# pong.net
KiCad netlist of a schematic drawn in EAGLE
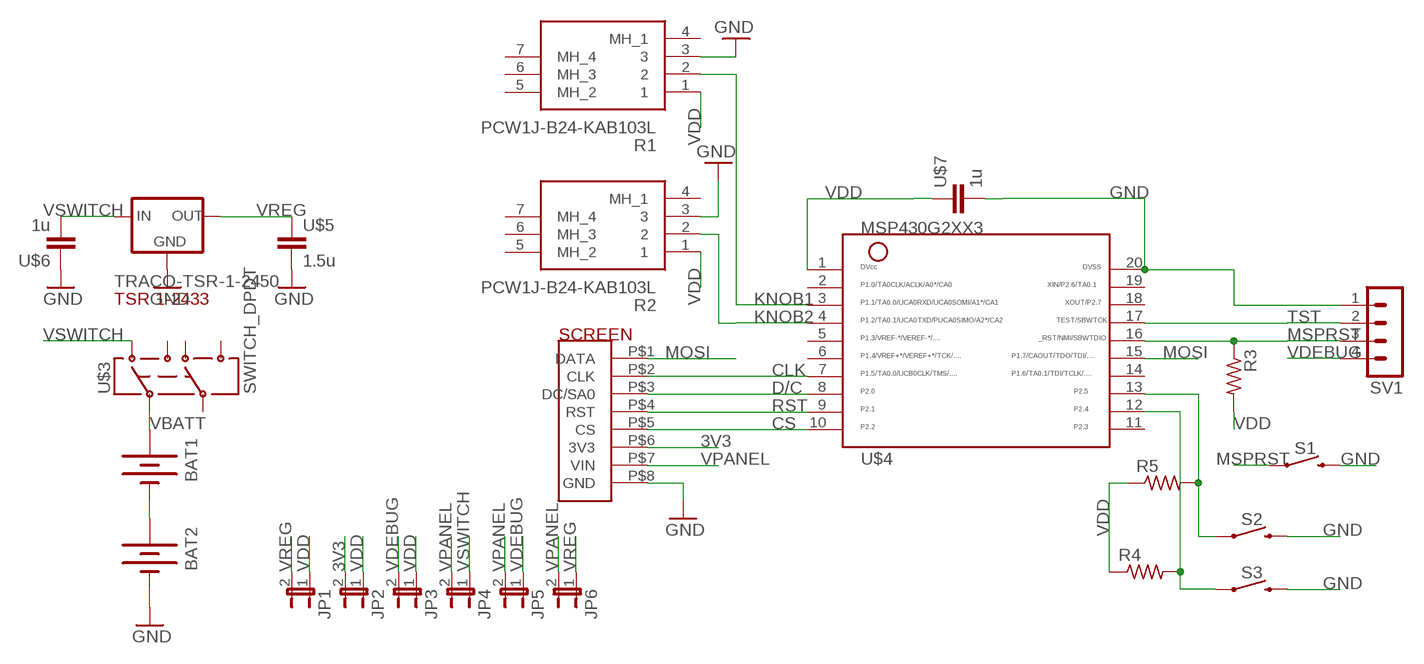
[diagram p0: schematic, sheet 1]

(export (version "E")
  (design (tool "Eeschema 10.0.6"))
  (components
    (comp (ref "BAT1")
      (value "BATTERY")
      (footprint "eagle-import:BATTERY_PACK_2AA")
      (libsource (lib "eagle-import") (part "BATTERY"))
    )
    (comp (ref "BAT2")
      (value "BATTERY")
      (footprint "eagle-import:BATTERY_PACK_2AA")
      (libsource (lib "eagle-import") (part "BATTERY"))
    )
    (comp (ref "JP1")
      (value "JP1E")
      (footprint "eagle-import:JP1")
      (libsource (lib "eagle-import") (part "JP1E"))
    )
    (comp (ref "JP2")
      (value "JP1E")
      (footprint "eagle-import:JP1")
      (libsource (lib "eagle-import") (part "JP1E"))
    )
    (comp (ref "JP3")
      (value "JP1E")
      (footprint "eagle-import:JP1")
      (libsource (lib "eagle-import") (part "JP1E"))
    )
    (comp (ref "JP4")
      (value "JP1E")
      (footprint "eagle-import:JP1")
      (libsource (lib "eagle-import") (part "JP1E"))
    )
    (comp (ref "JP5")
      (value "JP1E")
      (footprint "eagle-import:JP1")
      (libsource (lib "eagle-import") (part "JP1E"))
    )
    (comp (ref "JP6")
      (value "JP1E")
      (footprint "eagle-import:JP1")
      (libsource (lib "eagle-import") (part "JP1E"))
    )
    (comp (ref "R1")
      (value "PCW1J-B24-KAB103L")
      (footprint "eagle-import:PCW1JB24KAB103L")
      (fields
        (field (name "MOUSER_PART_NUMBER") "652-PCW1JB24KAB103L")
        (field (name "RS_PART_NUMBER") "1674561")
      )
      (libsource (lib "eagle-import") (part "PCW1J-B24-KAB103L"))
    )
    (comp (ref "R2")
      (value "PCW1J-B24-KAB103L")
      (footprint "eagle-import:PCW1JB24KAB103L")
      (fields
        (field (name "MOUSER_PART_NUMBER") "652-PCW1JB24KAB103L")
        (field (name "RS_PART_NUMBER") "1674561")
      )
      (libsource (lib "eagle-import") (part "PCW1J-B24-KAB103L"))
    )
    (comp (ref "R3")
      (value "47k")
      (footprint "eagle-import:R0805")
      (libsource (lib "eagle-import") (part "R-US_R0805"))
    )
    (comp (ref "R4")
      (value "47k")
      (footprint "eagle-import:R0805")
      (libsource (lib "eagle-import") (part "R-US_R0805"))
    )
    (comp (ref "R5")
      (value "47k")
      (footprint "eagle-import:R0805")
      (libsource (lib "eagle-import") (part "R-US_R0805"))
    )
    (comp (ref "S1")
      (value "MOMENTARY-SWITCH-SPST-PTH-6.0MM")
      (footprint "eagle-import:TACTILE_SWITCH_PTH_6.0MM")
      (libsource (lib "eagle-import") (part "MOMENTARY-SWITCH-SPST-PTH-6.0MM"))
    )
    (comp (ref "S2")
      (value "MOMENTARY-SWITCH-SPST-PTH-6.0MM")
      (footprint "eagle-import:TACTILE_SWITCH_PTH_6.0MM")
      (libsource (lib "eagle-import") (part "MOMENTARY-SWITCH-SPST-PTH-6.0MM"))
    )
    (comp (ref "S3")
      (value "MOMENTARY-SWITCH-SPST-PTH-6.0MM")
      (footprint "eagle-import:TACTILE_SWITCH_PTH_6.0MM")
      (libsource (lib "eagle-import") (part "MOMENTARY-SWITCH-SPST-PTH-6.0MM"))
    )
    (comp (ref "SV1")
      (value "4PINHEAD")
      (footprint "eagle-import:MA04-1")
      (libsource (lib "eagle-import") (part "4PINHEAD"))
    )
    (comp (ref "U$2")
      (value "SCREEN_HEADER")
      (footprint "eagle-import:SCREEN_FP")
      (libsource (lib "eagle-import") (part "SCREEN_HEADER"))
    )
    (comp (ref "U$3")
      (value "SWITCH_DPDT")
      (footprint "eagle-import:JS_DPDT_TH")
      (libsource (lib "eagle-import") (part "SWITCH_DPDT"))
    )
    (comp (ref "U$4")
      (value "MSP430G2XX3TSSOP")
      (footprint "eagle-import:PW20")
      (libsource (lib "eagle-import") (part "MSP430G2XX3TSSOP"))
    )
    (comp (ref "U$5")
      (value "1.5u")
      (footprint "eagle-import:RESC0805_N")
      (libsource (lib "eagle-import") (part "CAPACITOR_0805_N"))
    )
    (comp (ref "U$6")
      (value "1u")
      (footprint "eagle-import:RESC0805_N")
      (libsource (lib "eagle-import") (part "CAPACITOR_0805_N"))
    )
    (comp (ref "U$7")
      (value "1u")
      (footprint "eagle-import:RESC0805_N")
      (libsource (lib "eagle-import") (part "CAPACITOR_0805_N"))
    )
    (comp (ref "U$8")
      (value "TRACO-TSR-1-2450")
      (footprint "eagle-import:SIP3")
      (libsource (lib "eagle-import") (part "TRACO-TSR-1-2450"))
    )
  )
  (nets
    (net (code "1") (name "/3V3") (class "Default")
      (node (ref "JP2") (pin "2") (pinfunction "2_2") (pintype "passive"))
      (node (ref "U$2") (pin "P$6") (pinfunction "3V3_P$6") (pintype "bidirectional"))
    )
    (net (code "2") (name "/CLK") (class "Default")
      (node (ref "U$2") (pin "P$2") (pinfunction "CLK_P$2") (pintype "bidirectional"))
      (node (ref "U$4") (pin "7") (pinfunction "7_7") (pintype "bidirectional"))
    )
    (net (code "3") (name "/CS") (class "Default")
      (node (ref "U$2") (pin "P$5") (pinfunction "CS_P$5") (pintype "bidirectional"))
      (node (ref "U$4") (pin "10") (pinfunction "10_10") (pintype "bidirectional"))
    )
    (net (code "4") (name "/D{slash}C") (class "Default")
      (node (ref "U$2") (pin "P$3") (pinfunction "DC/SA0_P$3") (pintype "bidirectional"))
      (node (ref "U$4") (pin "8") (pinfunction "8_8") (pintype "bidirectional"))
    )
    (net (code "5") (name "/KNOB1") (class "Default")
      (node (ref "R1") (pin "2") (pinfunction "2_2") (pintype "bidirectional"))
      (node (ref "U$4") (pin "3") (pinfunction "3_3") (pintype "bidirectional"))
    )
    (net (code "6") (name "/KNOB2") (class "Default")
      (node (ref "R2") (pin "2") (pinfunction "2_2") (pintype "bidirectional"))
      (node (ref "U$4") (pin "4") (pinfunction "4_4") (pintype "bidirectional"))
    )
    (net (code "7") (name "/MOSI") (class "Default")
      (node (ref "U$2") (pin "P$1") (pinfunction "DATA_P$1") (pintype "bidirectional"))
      (node (ref "U$4") (pin "15") (pinfunction "15_15") (pintype "bidirectional"))
    )
    (net (code "8") (name "/MSPRST") (class "Default")
      (node (ref "R3") (pin "1") (pinfunction "1_1") (pintype "passive"))
      (node (ref "S1") (pin "1") (pinfunction "1_1") (pintype "passive"))
      (node (ref "SV1") (pin "3") (pinfunction "3_3") (pintype "passive"))
      (node (ref "U$4") (pin "16") (pinfunction "16_16") (pintype "bidirectional"))
    )
    (net (code "9") (name "/RST") (class "Default")
      (node (ref "U$2") (pin "P$4") (pinfunction "RST_P$4") (pintype "bidirectional"))
      (node (ref "U$4") (pin "9") (pinfunction "9_9") (pintype "bidirectional"))
    )
    (net (code "10") (name "/TST") (class "Default")
      (node (ref "SV1") (pin "2") (pinfunction "2_2") (pintype "passive"))
      (node (ref "U$4") (pin "17") (pinfunction "17_17") (pintype "bidirectional"))
    )
    (net (code "11") (name "/VBATT") (class "Default")
      (node (ref "BAT1") (pin "3V") (pinfunction "+_3V") (pintype "power_in"))
      (node (ref "U$3") (pin "2") (pinfunction "2_2") (pintype "bidirectional"))
    )
    (net (code "12") (name "/VDD") (class "Default")
      (node (ref "JP1") (pin "1") (pinfunction "1_1") (pintype "passive"))
      (node (ref "JP2") (pin "1") (pinfunction "1_1") (pintype "passive"))
      (node (ref "JP3") (pin "1") (pinfunction "1_1") (pintype "passive"))
      (node (ref "R1") (pin "1") (pinfunction "1_1") (pintype "bidirectional"))
      (node (ref "R2") (pin "1") (pinfunction "1_1") (pintype "bidirectional"))
      (node (ref "R3") (pin "2") (pinfunction "2_2") (pintype "passive"))
      (node (ref "R4") (pin "1") (pinfunction "1_1") (pintype "passive"))
      (node (ref "R5") (pin "1") (pinfunction "1_1") (pintype "passive"))
      (node (ref "U$4") (pin "1") (pinfunction "1_1") (pintype "bidirectional"))
      (node (ref "U$7") (pin "1") (pinfunction "1_1") (pintype "passive"))
    )
    (net (code "13") (name "/VDEBUG") (class "Default")
      (node (ref "JP3") (pin "2") (pinfunction "2_2") (pintype "passive"))
      (node (ref "JP5") (pin "1") (pinfunction "1_1") (pintype "passive"))
      (node (ref "SV1") (pin "4") (pinfunction "4_4") (pintype "passive"))
    )
    (net (code "14") (name "/VPANEL") (class "Default")
      (node (ref "JP4") (pin "2") (pinfunction "2_2") (pintype "passive"))
      (node (ref "JP5") (pin "2") (pinfunction "2_2") (pintype "passive"))
      (node (ref "JP6") (pin "2") (pinfunction "2_2") (pintype "passive"))
      (node (ref "U$2") (pin "P$7") (pinfunction "VIN_P$7") (pintype "bidirectional"))
    )
    (net (code "15") (name "/VREG") (class "Default")
      (node (ref "JP1") (pin "2") (pinfunction "2_2") (pintype "passive"))
      (node (ref "JP6") (pin "1") (pinfunction "1_1") (pintype "passive"))
      (node (ref "U$5") (pin "1") (pinfunction "1_1") (pintype "passive"))
      (node (ref "U$8") (pin "3") (pinfunction "OUT_3") (pintype "passive"))
    )
    (net (code "16") (name "/VSWITCH") (class "Default")
      (node (ref "JP4") (pin "1") (pinfunction "1_1") (pintype "passive"))
      (node (ref "U$3") (pin "1") (pinfunction "1_1") (pintype "bidirectional"))
      (node (ref "U$6") (pin "2") (pinfunction "2_2") (pintype "passive"))
      (node (ref "U$8") (pin "1") (pinfunction "IN_1") (pintype "input"))
    )
    (net (code "17") (name "GND") (class "Default")
      (node (ref "BAT2") (pin "GND") (pinfunction "-_GND") (pintype "power_in"))
      (node (ref "R1") (pin "3") (pinfunction "3_3") (pintype "bidirectional"))
      (node (ref "R2") (pin "3") (pinfunction "3_3") (pintype "bidirectional"))
      (node (ref "S1") (pin "3") (pinfunction "2_3") (pintype "passive"))
      (node (ref "S2") (pin "3") (pinfunction "2_3") (pintype "passive"))
      (node (ref "S3") (pin "3") (pinfunction "2_3") (pintype "passive"))
      (node (ref "SV1") (pin "1") (pinfunction "1_1") (pintype "passive"))
      (node (ref "U$2") (pin "P$8") (pinfunction "GND_P$8") (pintype "bidirectional"))
      (node (ref "U$4") (pin "20") (pinfunction "20_20") (pintype "bidirectional"))
      (node (ref "U$5") (pin "2") (pinfunction "2_2") (pintype "passive"))
      (node (ref "U$6") (pin "1") (pinfunction "1_1") (pintype "passive"))
      (node (ref "U$7") (pin "2") (pinfunction "2_2") (pintype "passive"))
      (node (ref "U$8") (pin "2") (pinfunction "GND_2") (pintype "input"))
    )
    (net (code "18") (name "Net-(BAT1--)") (class "Default")
      (node (ref "BAT1") (pin "GND") (pinfunction "-_GND") (pintype "power_in"))
      (node (ref "BAT2") (pin "3V") (pinfunction "+_3V") (pintype "power_in"))
    )
    (net (code "19") (name "Net-(R4-Pad2)") (class "Default")
      (node (ref "R4") (pin "2") (pinfunction "2_2") (pintype "passive"))
      (node (ref "S3") (pin "1") (pinfunction "1_1") (pintype "passive"))
      (node (ref "U$4") (pin "12") (pinfunction "12_12") (pintype "bidirectional"))
    )
    (net (code "20") (name "Net-(R5-Pad2)") (class "Default")
      (node (ref "R5") (pin "2") (pinfunction "2_2") (pintype "passive"))
      (node (ref "S2") (pin "1") (pinfunction "1_1") (pintype "passive"))
      (node (ref "U$4") (pin "13") (pinfunction "13_13") (pintype "bidirectional"))
    )
    (net (code "21") (name "unconnected-(R1-MH_1-Pad4)") (class "Default")
      (node (ref "R1") (pin "4") (pinfunction "MH_1_4") (pintype "bidirectional"))
    )
    (net (code "22") (name "unconnected-(R1-MH_2-Pad5)") (class "Default")
      (node (ref "R1") (pin "5") (pinfunction "MH_2_5") (pintype "bidirectional"))
    )
    (net (code "23") (name "unconnected-(R1-MH_3-Pad6)") (class "Default")
      (node (ref "R1") (pin "6") (pinfunction "MH_3_6") (pintype "bidirectional"))
    )
    (net (code "24") (name "unconnected-(R1-MH_4-Pad7)") (class "Default")
      (node (ref "R1") (pin "7") (pinfunction "MH_4_7") (pintype "bidirectional"))
    )
    (net (code "25") (name "unconnected-(R2-MH_1-Pad4)") (class "Default")
      (node (ref "R2") (pin "4") (pinfunction "MH_1_4") (pintype "bidirectional"))
    )
    (net (code "26") (name "unconnected-(R2-MH_2-Pad5)") (class "Default")
      (node (ref "R2") (pin "5") (pinfunction "MH_2_5") (pintype "bidirectional"))
    )
    (net (code "27") (name "unconnected-(R2-MH_3-Pad6)") (class "Default")
      (node (ref "R2") (pin "6") (pinfunction "MH_3_6") (pintype "bidirectional"))
    )
    (net (code "28") (name "unconnected-(R2-MH_4-Pad7)") (class "Default")
      (node (ref "R2") (pin "7") (pinfunction "MH_4_7") (pintype "bidirectional"))
    )
    (net (code "29") (name "unconnected-(U$3-Pad3)") (class "Default")
      (node (ref "U$3") (pin "3") (pinfunction "3_3") (pintype "bidirectional"))
    )
    (net (code "30") (name "unconnected-(U$3-Pad4)") (class "Default")
      (node (ref "U$3") (pin "4") (pinfunction "4_4") (pintype "bidirectional"))
    )
    (net (code "31") (name "unconnected-(U$3-Pad5)") (class "Default")
      (node (ref "U$3") (pin "5") (pinfunction "5_5") (pintype "bidirectional"))
    )
    (net (code "32") (name "unconnected-(U$3-Pad6)") (class "Default")
      (node (ref "U$3") (pin "6") (pinfunction "6_6") (pintype "bidirectional"))
    )
    (net (code "33") (name "unconnected-(U$4-Pad2)") (class "Default")
      (node (ref "U$4") (pin "2") (pinfunction "2_2") (pintype "bidirectional"))
    )
    (net (code "34") (name "unconnected-(U$4-Pad5)") (class "Default")
      (node (ref "U$4") (pin "5") (pinfunction "5_5") (pintype "bidirectional"))
    )
    (net (code "35") (name "unconnected-(U$4-Pad6)") (class "Default")
      (node (ref "U$4") (pin "6") (pinfunction "6_6") (pintype "bidirectional"))
    )
    (net (code "36") (name "unconnected-(U$4-Pad11)") (class "Default")
      (node (ref "U$4") (pin "11") (pinfunction "11_11") (pintype "bidirectional"))
    )
    (net (code "37") (name "unconnected-(U$4-Pad14)") (class "Default")
      (node (ref "U$4") (pin "14") (pinfunction "14_14") (pintype "bidirectional"))
    )
    (net (code "38") (name "unconnected-(U$4-Pad18)") (class "Default")
      (node (ref "U$4") (pin "18") (pinfunction "18_18") (pintype "bidirectional"))
    )
    (net (code "39") (name "unconnected-(U$4-Pad19)") (class "Default")
      (node (ref "U$4") (pin "19") (pinfunction "19_19") (pintype "bidirectional"))
    )
  )
)
